# USB3A1P_0v0.net
KiCad netlist of a schematic drawn in EAGLE
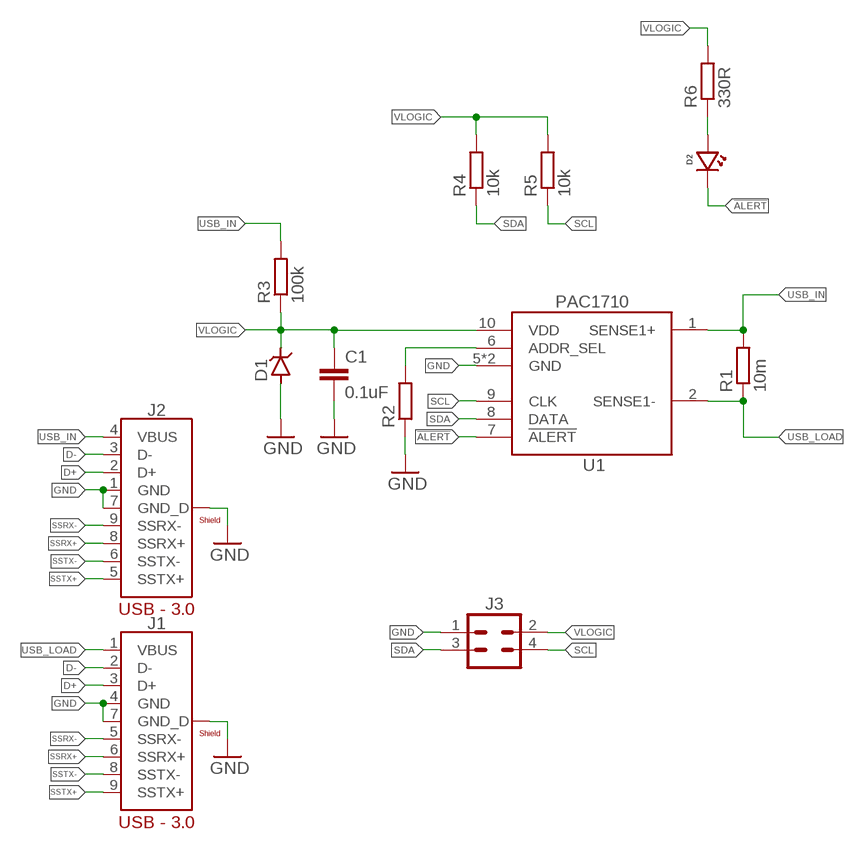
[diagram p0: schematic, sheet 1]

(export (version "E")
  (design (tool "Eeschema 10.0.6"))
  (components
    (comp (ref "C1")
      (value "0.1uF")
      (footprint "eagle-import:C0603")
      (fields (field (name "MF") "Murata") (field (name "MPN") "GCM188R71E104KA57D"))
      (libsource (lib "eagle-import") (part "C-EUC06030.1UF"))
    )
    (comp (ref "D1")
      (value "DIODE_ZENERSOD-123")
      (footprint "eagle-import:SOD-123")
      (libsource (lib "eagle-import") (part "DIODE_ZENERSOD-123"))
    )
    (comp (ref "D2")
      (value "LED1206_BOTTOM")
      (footprint "eagle-import:LED_1206_BOTTOM")
      (libsource (lib "eagle-import") (part "LED1206_BOTTOM"))
    )
    (comp (ref "J1")
      (value "USB_3.0FEMALE_TENSILITY")
      (footprint "eagle-import:USB_A_3.0_FEMALE_TENSILITY")
      (fields (field (name "MF") "Tensility") (field (name "MPN") "54-00007"))
      (libsource (lib "eagle-import") (part "USB_3.0FEMALE_TENSILITY"))
    )
    (comp (ref "J2")
      (value "USB_3.0MALE_TENSILITY")
      (footprint "eagle-import:USB_A_3.0_MALE_TENSILITY")
      (fields (field (name "MF") "Tensility") (field (name "MPN") "50-00469"))
      (libsource (lib "eagle-import") (part "USB_3.0MALE_TENSILITY"))
    )
    (comp (ref "J3")
      (value "CONN_2X2MIRCOFIT_RT")
      (footprint "eagle-import:2X2_MICROFIT_RT")
      (fields (field (name "MF") "Molex") (field (name "MPN") "0430450400"))
      (libsource (lib "eagle-import") (part "CONN_2X2MIRCOFIT_RT"))
    )
    (comp (ref "R1")
      (value "10m")
      (footprint "eagle-import:R0805")
      (fields (field (name "MF") "Bourns") (field (name "MPN") "CRF0805-FZ-R010ELF"))
      (libsource (lib "eagle-import") (part "R-EU_R08050.01"))
    )
    (comp (ref "R2")
      (value "R-EU_R0603")
      (footprint "eagle-import:R0603")
      (fields (field (name "MF") "Yageo"))
      (libsource (lib "eagle-import") (part "R-EU_R0603"))
    )
    (comp (ref "R3")
      (value "100k")
      (footprint "eagle-import:R0603")
      (fields (field (name "MF") "Yageo") (field (name "MPN") "RC0603FR-07100KL"))
      (libsource (lib "eagle-import") (part "R-EU_R0603100K"))
    )
    (comp (ref "R4")
      (value "10k")
      (footprint "eagle-import:R0603")
      (fields (field (name "MF") "Yageo") (field (name "MPN") "RC0603FR-0710KL"))
      (libsource (lib "eagle-import") (part "R-EU_R060310K"))
    )
    (comp (ref "R5")
      (value "10k")
      (footprint "eagle-import:R0603")
      (fields (field (name "MF") "Yageo") (field (name "MPN") "RC0603FR-0710KL"))
      (libsource (lib "eagle-import") (part "R-EU_R060310K"))
    )
    (comp (ref "R6")
      (value "330R")
      (footprint "eagle-import:R0603")
      (fields
        (field (name "MF") "Yageo")
        (field (name "MPN") "RC0603FR-07330RL")
        (field (name "VALUE_PART") "330")
      )
      (libsource (lib "eagle-import") (part "R-EU_R0603330"))
    )
    (comp (ref "U1")
      (value "PAC1710")
      (footprint "eagle-import:VDFN-10")
      (fields (field (name "MF") "Microchip") (field (name "MPN") "PAC1710-1-AIA-TR"))
      (libsource (lib "eagle-import") (part "PAC1710"))
    )
  )
  (nets
    (net (code "1") (name "/~{ALERT}") (class "Default")
      (node (ref "D2") (pin "CATHODE") (pinfunction "CATHODE_CATHODE") (pintype "power_in"))
      (node (ref "U1") (pin "7") (pinfunction "~{ALERT}_7") (pintype "output"))
    )
    (net (code "2") (name "D+") (class "Default")
      (node (ref "J1") (pin "3") (pinfunction "D+_3") (pintype "bidirectional"))
      (node (ref "J2") (pin "2") (pinfunction "D+_2") (pintype "bidirectional"))
    )
    (net (code "3") (name "D-") (class "Default")
      (node (ref "J1") (pin "2") (pinfunction "D-_2") (pintype "bidirectional"))
      (node (ref "J2") (pin "3") (pinfunction "D-_3") (pintype "bidirectional"))
    )
    (net (code "4") (name "GND") (class "Default")
      (node (ref "C1") (pin "2") (pinfunction "2_2") (pintype "passive"))
      (node (ref "D1") (pin "ANODE") (pinfunction "A_ANODE") (pintype "passive"))
      (node (ref "J1") (pin "4") (pinfunction "GND_4") (pintype "power_in"))
      (node (ref "J1") (pin "7") (pinfunction "GND_D_7") (pintype "power_in"))
      (node (ref "J1") (pin "BODY@1") (pinfunction "SHIELD_BODY@1") (pintype "bidirectional"))
      (node (ref "J1") (pin "BODY@2") (pinfunction "SHIELD_BODY@2") (pintype "bidirectional"))
      (node (ref "J2") (pin "1") (pinfunction "GND_1") (pintype "power_in"))
      (node (ref "J2") (pin "7") (pinfunction "GND_D_7") (pintype "power_in"))
      (node (ref "J2") (pin "BODY@1") (pinfunction "SHIELD_BODY@1") (pintype "bidirectional"))
      (node (ref "J2") (pin "BODY@2") (pinfunction "SHIELD_BODY@2") (pintype "bidirectional"))
      (node (ref "J2") (pin "BODY@3") (pinfunction "SHIELD_BODY@3") (pintype "bidirectional"))
      (node (ref "J2") (pin "BODY@4") (pinfunction "SHIELD_BODY@4") (pintype "bidirectional"))
      (node (ref "J3") (pin "1") (pinfunction "1_1") (pintype "bidirectional"))
      (node (ref "R2") (pin "1") (pinfunction "1_1") (pintype "passive"))
      (node (ref "U1") (pin "5") (pinfunction "GND_5") (pintype "power_in"))
      (node (ref "U1") (pin "EP") (pinfunction "GND_EP") (pintype "power_in"))
    )
    (net (code "5") (name "Net-(D2-PadANODE)") (class "Default")
      (node (ref "D2") (pin "ANODE") (pinfunction "ANODE_ANODE") (pintype "power_in"))
      (node (ref "R6") (pin "1") (pinfunction "1_1") (pintype "passive"))
    )
    (net (code "6") (name "Net-(U1-ADDR_SEL)") (class "Default")
      (node (ref "R2") (pin "2") (pinfunction "2_2") (pintype "passive"))
      (node (ref "U1") (pin "6") (pinfunction "ADDR_SEL_6") (pintype "input"))
    )
    (net (code "7") (name "SCL") (class "Default")
      (node (ref "J3") (pin "4") (pinfunction "4_4") (pintype "bidirectional"))
      (node (ref "R5") (pin "1") (pinfunction "1_1") (pintype "passive"))
      (node (ref "U1") (pin "9") (pinfunction "CLK_9") (pintype "input"))
    )
    (net (code "8") (name "SDA") (class "Default")
      (node (ref "J3") (pin "3") (pinfunction "3_3") (pintype "bidirectional"))
      (node (ref "R4") (pin "1") (pinfunction "1_1") (pintype "passive"))
      (node (ref "U1") (pin "8") (pinfunction "DATA_8") (pintype "bidirectional"))
    )
    (net (code "9") (name "SSRX+") (class "Default")
      (node (ref "J1") (pin "6") (pinfunction "SSRX+_6") (pintype "bidirectional"))
      (node (ref "J2") (pin "8") (pinfunction "SSRX+_8") (pintype "bidirectional"))
    )
    (net (code "10") (name "SSRX-") (class "Default")
      (node (ref "J1") (pin "5") (pinfunction "SSRX-_5") (pintype "bidirectional"))
      (node (ref "J2") (pin "9") (pinfunction "SSRX-_9") (pintype "bidirectional"))
    )
    (net (code "11") (name "SSTX+") (class "Default")
      (node (ref "J1") (pin "9") (pinfunction "SSTX+_9") (pintype "bidirectional"))
      (node (ref "J2") (pin "5") (pinfunction "SSTX+_5") (pintype "bidirectional"))
    )
    (net (code "12") (name "SSTX-") (class "Default")
      (node (ref "J1") (pin "8") (pinfunction "SSTX-_8") (pintype "bidirectional"))
      (node (ref "J2") (pin "6") (pinfunction "SSTX-_6") (pintype "bidirectional"))
    )
    (net (code "13") (name "USB_IN") (class "Default")
      (node (ref "J2") (pin "4") (pinfunction "VBUS_4") (pintype "power_in"))
      (node (ref "R1") (pin "2") (pinfunction "2_2") (pintype "passive"))
      (node (ref "R3") (pin "2") (pinfunction "2_2") (pintype "passive"))
      (node (ref "U1") (pin "1") (pinfunction "SENSE1+_1") (pintype "input"))
    )
    (net (code "14") (name "USB_LOAD") (class "Default")
      (node (ref "J1") (pin "1") (pinfunction "VBUS_1") (pintype "power_in"))
      (node (ref "R1") (pin "1") (pinfunction "1_1") (pintype "passive"))
      (node (ref "U1") (pin "2") (pinfunction "SENSE1-_2") (pintype "input"))
    )
    (net (code "15") (name "VLOGIC") (class "Default")
      (node (ref "C1") (pin "1") (pinfunction "1_1") (pintype "passive"))
      (node (ref "D1") (pin "CAT") (pinfunction "C_CAT") (pintype "passive"))
      (node (ref "J3") (pin "2") (pinfunction "2_2") (pintype "bidirectional"))
      (node (ref "R3") (pin "1") (pinfunction "1_1") (pintype "passive"))
      (node (ref "R4") (pin "2") (pinfunction "2_2") (pintype "passive"))
      (node (ref "R5") (pin "2") (pinfunction "2_2") (pintype "passive"))
      (node (ref "R6") (pin "2") (pinfunction "2_2") (pintype "passive"))
      (node (ref "U1") (pin "10") (pinfunction "VDD_10") (pintype "power_in"))
    )
  )
)
